# schematic.net
KiCad netlist of a schematic drawn in Altium Designer
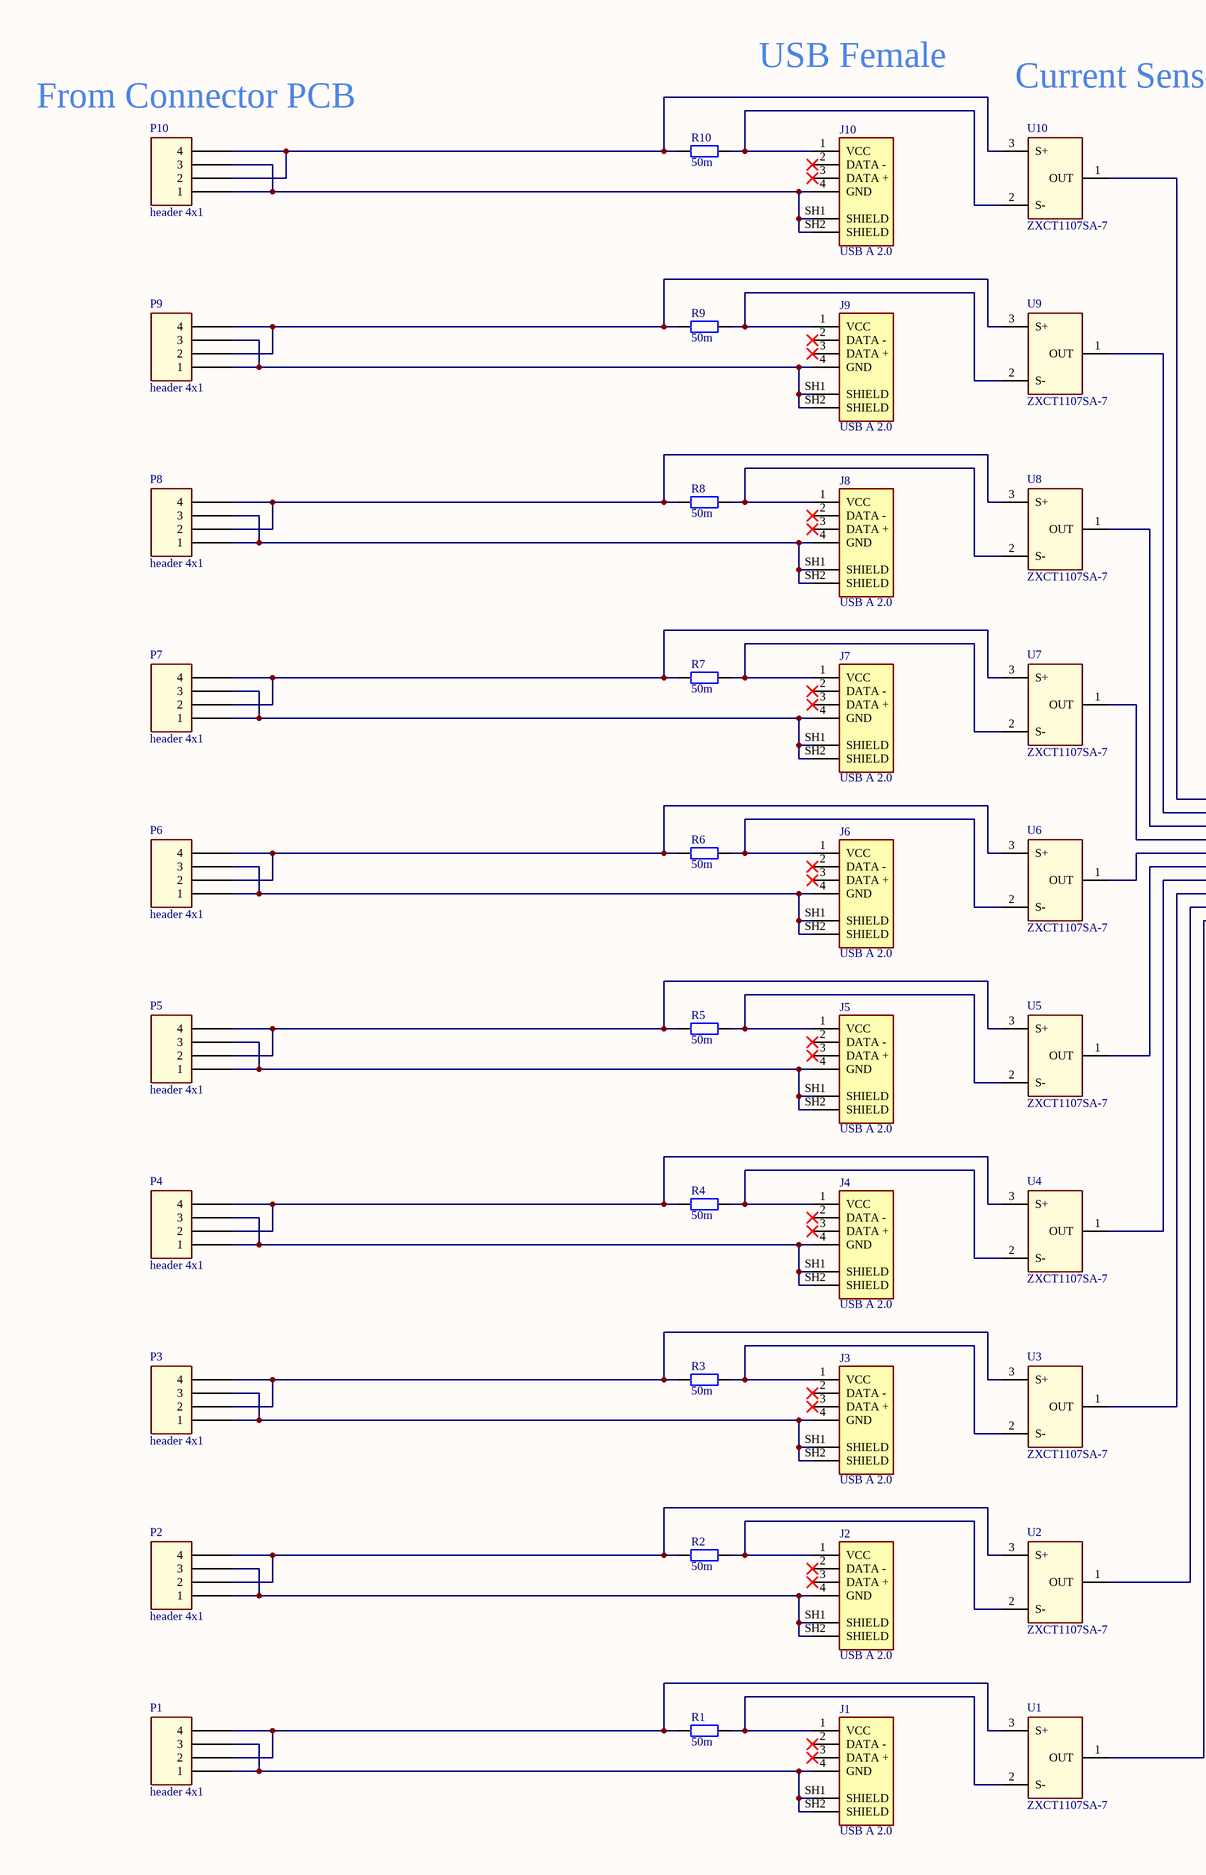
[diagram p0: schematic.SchDoc, left]
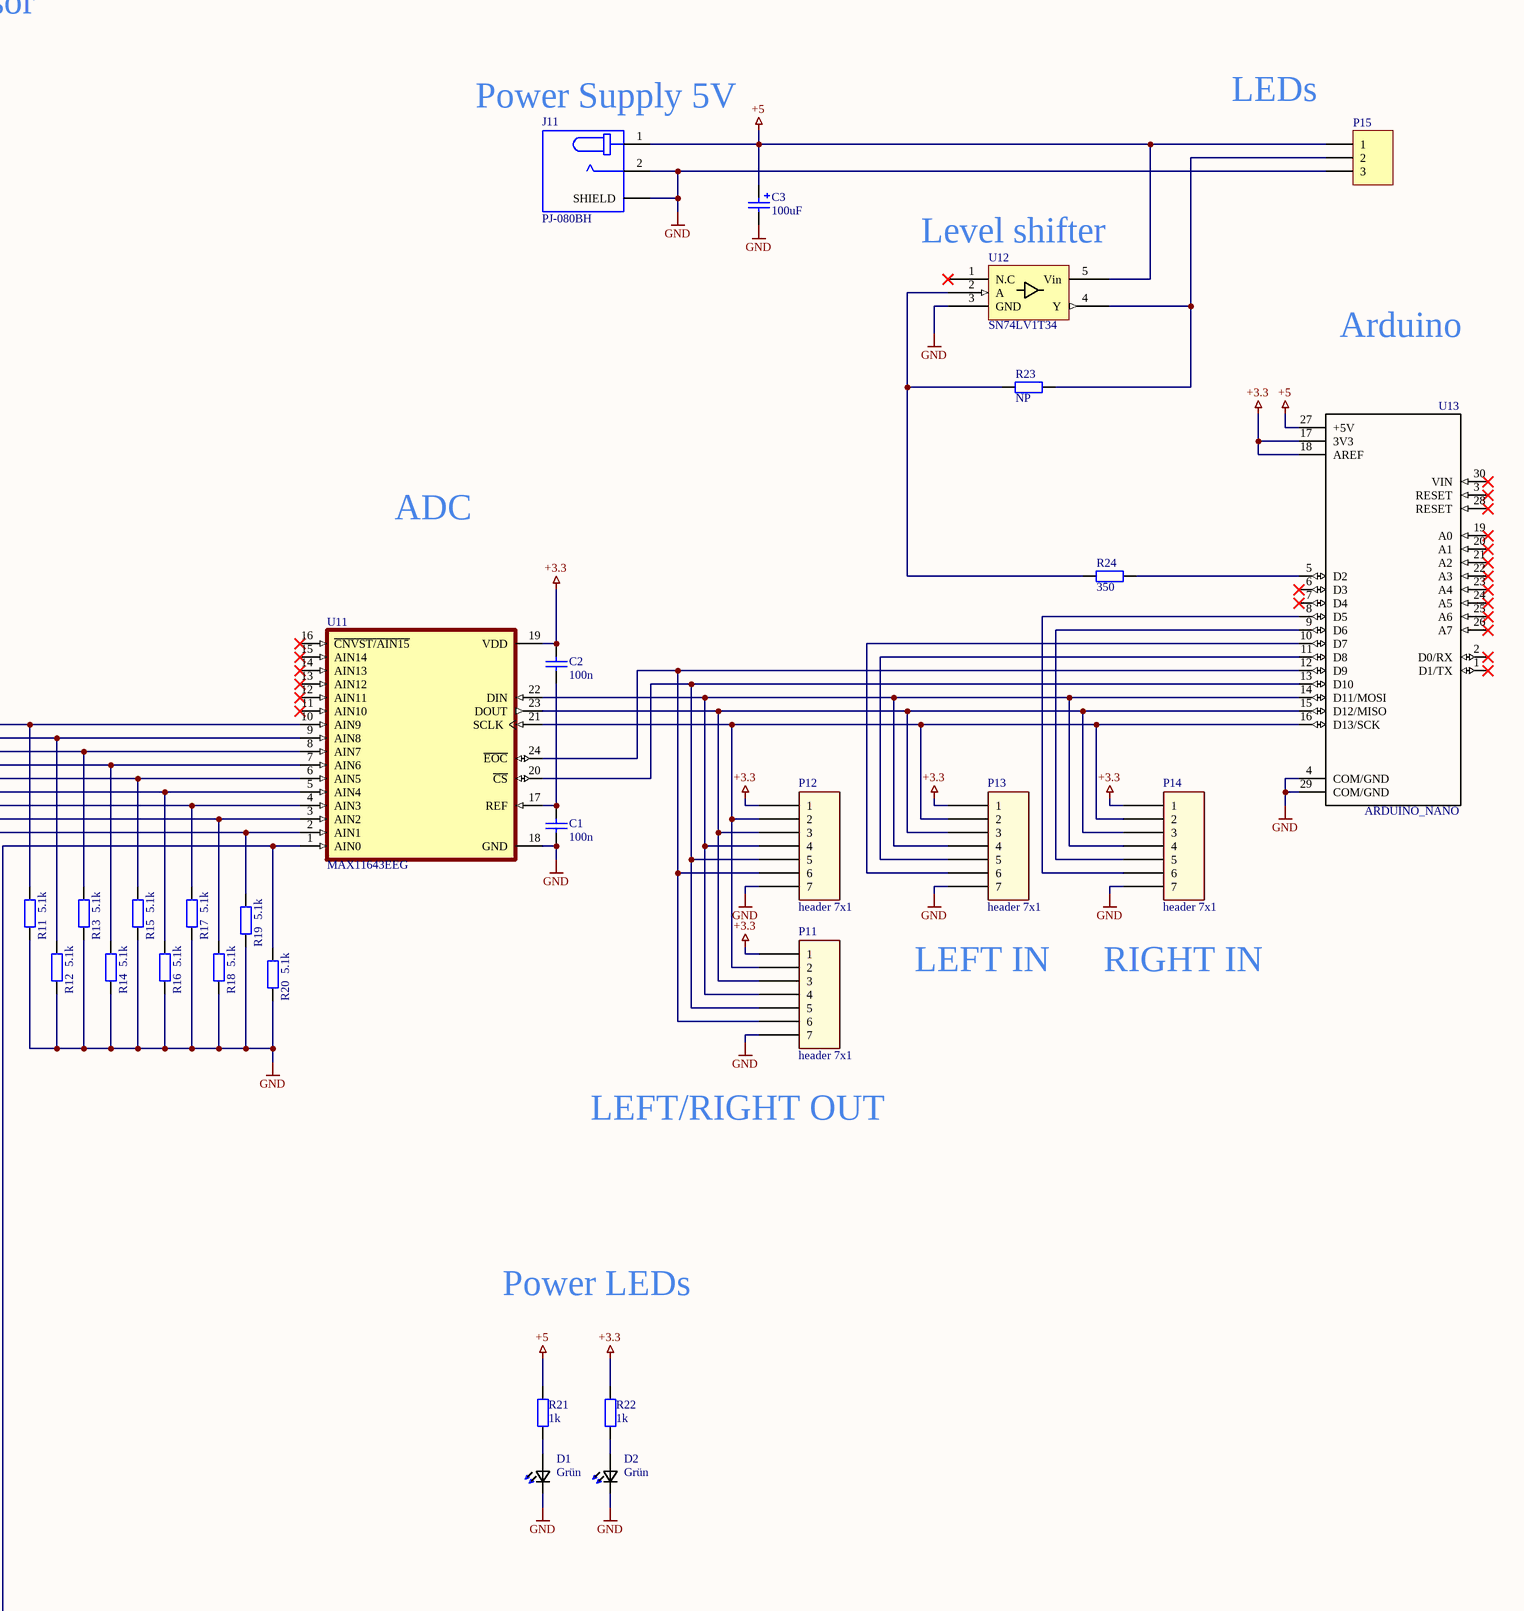
[diagram p1: schematic.SchDoc, right]

(export (version "E")
  (design (tool "Eeschema 10.0.6"))
  (components
    (comp (ref "C1")
      (value "100n")
      (footprint "CAP_0603i_1608m -N")
      (description "capacitor")
      (libsource (lib "IDSC std generic parts") (part "Cap"))
    )
    (comp (ref "C2")
      (value "100n")
      (footprint "CAP_0603i_1608m -N")
      (description "capacitor")
      (libsource (lib "IDSC std generic parts") (part "Cap"))
    )
    (comp (ref "C3")
      (value "100uF")
      (footprint "Cap_F-Type-Package")
      (description "Polarised capacitor (e.g. Electrolytic )")
      (libsource (lib "IDSC std generic parts") (part "Cap pol"))
    )
    (comp (ref "D1")
      (value "Grün")
      (footprint "*0603")
      (description "LED; SMD; 0603; gr黱; 35mcd; 1.6x0.8x0.55mm; 130掳; 2梅2.V; 20mA")
      (fields (field (name "MP") "LTST-C191KGKT") (field (name "DIGI-KEY_PART_NUMBER") "160-1446-1-ND"))
      (libsource (lib "Funk") (part "LTST-C191KGKT"))
    )
    (comp (ref "D2")
      (value "Grün")
      (footprint "*0603")
      (description "LED; SMD; 0603; gr黱; 35mcd; 1.6x0.8x0.55mm; 130掳; 2梅2.V; 20mA")
      (fields (field (name "MP") "LTST-C191KGKT") (field (name "DIGI-KEY_PART_NUMBER") "160-1446-1-ND"))
      (libsource (lib "Funk") (part "LTST-C191KGKT"))
    )
    (comp (ref "J1")
      (value "USB A 2.0")
      (footprint "54-00005")
      (description "Type A, USB 2.0, 1 A, Vertical, Through Hole, USB Receptacle")
      (fields (field (name "MP") "UJ2-AV-2-TH") (field (name "MF") "CUI Devices"))
      (libsource (lib "USBHUB") (part "USB A 2.0"))
    )
    (comp (ref "J2")
      (value "USB A 2.0")
      (footprint "54-00005")
      (description "Type A, USB 2.0, 1 A, Vertical, Through Hole, USB Receptacle")
      (fields (field (name "MP") "UJ2-AV-2-TH") (field (name "MF") "CUI Devices"))
      (libsource (lib "USBHUB") (part "USB A 2.0"))
    )
    (comp (ref "J3")
      (value "USB A 2.0")
      (footprint "54-00005")
      (description "Type A, USB 2.0, 1 A, Vertical, Through Hole, USB Receptacle")
      (fields (field (name "MP") "UJ2-AV-2-TH") (field (name "MF") "CUI Devices"))
      (libsource (lib "USBHUB") (part "USB A 2.0"))
    )
    (comp (ref "J4")
      (value "USB A 2.0")
      (footprint "54-00005")
      (description "Type A, USB 2.0, 1 A, Vertical, Through Hole, USB Receptacle")
      (fields (field (name "MP") "UJ2-AV-2-TH") (field (name "MF") "CUI Devices"))
      (libsource (lib "USBHUB") (part "USB A 2.0"))
    )
    (comp (ref "J5")
      (value "USB A 2.0")
      (footprint "54-00005")
      (description "Type A, USB 2.0, 1 A, Vertical, Through Hole, USB Receptacle")
      (fields (field (name "MP") "UJ2-AV-2-TH") (field (name "MF") "CUI Devices"))
      (libsource (lib "USBHUB") (part "USB A 2.0"))
    )
    (comp (ref "J6")
      (value "USB A 2.0")
      (footprint "54-00005")
      (description "Type A, USB 2.0, 1 A, Vertical, Through Hole, USB Receptacle")
      (fields (field (name "MP") "UJ2-AV-2-TH") (field (name "MF") "CUI Devices"))
      (libsource (lib "USBHUB") (part "USB A 2.0"))
    )
    (comp (ref "J7")
      (value "USB A 2.0")
      (footprint "54-00005")
      (description "Type A, USB 2.0, 1 A, Vertical, Through Hole, USB Receptacle")
      (fields (field (name "MP") "UJ2-AV-2-TH") (field (name "MF") "CUI Devices"))
      (libsource (lib "USBHUB") (part "USB A 2.0"))
    )
    (comp (ref "J8")
      (value "USB A 2.0")
      (footprint "54-00005")
      (description "Type A, USB 2.0, 1 A, Vertical, Through Hole, USB Receptacle")
      (fields (field (name "MP") "UJ2-AV-2-TH") (field (name "MF") "CUI Devices"))
      (libsource (lib "USBHUB") (part "USB A 2.0"))
    )
    (comp (ref "J9")
      (value "USB A 2.0")
      (footprint "54-00005")
      (description "Type A, USB 2.0, 1 A, Vertical, Through Hole, USB Receptacle")
      (fields (field (name "MP") "UJ2-AV-2-TH") (field (name "MF") "CUI Devices"))
      (libsource (lib "USBHUB") (part "USB A 2.0"))
    )
    (comp (ref "J10")
      (value "USB A 2.0")
      (footprint "54-00005")
      (description "Type A, USB 2.0, 1 A, Vertical, Through Hole, USB Receptacle")
      (fields (field (name "MP") "UJ2-AV-2-TH") (field (name "MF") "CUI Devices"))
      (libsource (lib "USBHUB") (part "USB A 2.0"))
    )
    (comp (ref "J11")
      (value "PJ-080BH")
      (footprint "CUI_PJ-080BH")
      (description "2.5 x 6.4 mm, 10.0 A, Horizontal, Through Hole, Shielded, Dc Power Jack Connector")
      (fields (field (name "MF") "CUI Devices"))
      (libsource (lib "USBHUB") (part "PJ-080BH"))
    )
    (comp (ref "P1")
      (value "header 4x1")
      (footprint "4x1, 2.54mm, smd")
      (libsource (lib "USBHUB") (part "header 4x1"))
    )
    (comp (ref "P2")
      (value "header 4x1")
      (footprint "4x1, 2.54mm, smd")
      (libsource (lib "USBHUB") (part "header 4x1"))
    )
    (comp (ref "P3")
      (value "header 4x1")
      (footprint "4x1, 2.54mm, smd")
      (libsource (lib "USBHUB") (part "header 4x1"))
    )
    (comp (ref "P4")
      (value "header 4x1")
      (footprint "4x1, 2.54mm, smd")
      (libsource (lib "USBHUB") (part "header 4x1"))
    )
    (comp (ref "P5")
      (value "header 4x1")
      (footprint "4x1, 2.54mm, smd")
      (libsource (lib "USBHUB") (part "header 4x1"))
    )
    (comp (ref "P6")
      (value "header 4x1")
      (footprint "4x1, 2.54mm, smd")
      (libsource (lib "USBHUB") (part "header 4x1"))
    )
    (comp (ref "P7")
      (value "header 4x1")
      (footprint "4x1, 2.54mm, smd")
      (libsource (lib "USBHUB") (part "header 4x1"))
    )
    (comp (ref "P8")
      (value "header 4x1")
      (footprint "4x1, 2.54mm, smd")
      (libsource (lib "USBHUB") (part "header 4x1"))
    )
    (comp (ref "P9")
      (value "header 4x1")
      (footprint "4x1, 2.54mm, smd")
      (libsource (lib "USBHUB") (part "header 4x1"))
    )
    (comp (ref "P10")
      (value "header 4x1")
      (footprint "4x1, 2.54mm, smd")
      (libsource (lib "USBHUB") (part "header 4x1"))
    )
    (comp (ref "P11")
      (value "header 7x1")
      (footprint "7 pin, 3.5mm")
      (description "right out")
      (libsource (lib "USBHUB") (part "header 7x1"))
    )
    (comp (ref "P12")
      (value "header 7x1")
      (footprint "7 pin, 3.5mm")
      (description "left out")
      (libsource (lib "USBHUB") (part "header 7x1"))
    )
    (comp (ref "P13")
      (value "header 7x1")
      (footprint "7 pin, 3.5mm")
      (description "left in")
      (libsource (lib "USBHUB") (part "header 7x1"))
    )
    (comp (ref "P14")
      (value "header 7x1")
      (footprint "7 pin, 3.5mm")
      (description "right in")
      (libsource (lib "USBHUB") (part "header 7x1"))
    )
    (comp (ref "P15")
      (value "Header 3")
      (footprint "3.5MM Phoenix Contact 1751251")
      (description "Header, 3-Pin")
      (libsource (lib "IDSC std connectors") (part "Header 3"))
    )
    (comp (ref "R1")
      (value "50m")
      (footprint "RES_0805i_2012m -N")
      (description "Resistor")
      (libsource (lib "IDSC std generic parts") (part "Res"))
    )
    (comp (ref "R2")
      (value "50m")
      (footprint "RES_0805i_2012m -N")
      (description "Resistor")
      (libsource (lib "IDSC std generic parts") (part "Res"))
    )
    (comp (ref "R3")
      (value "50m")
      (footprint "RES_0805i_2012m -N")
      (description "Resistor")
      (libsource (lib "IDSC std generic parts") (part "Res"))
    )
    (comp (ref "R4")
      (value "50m")
      (footprint "RES_0805i_2012m -N")
      (description "Resistor")
      (libsource (lib "IDSC std generic parts") (part "Res"))
    )
    (comp (ref "R5")
      (value "50m")
      (footprint "RES_0805i_2012m -N")
      (description "Resistor")
      (libsource (lib "IDSC std generic parts") (part "Res"))
    )
    (comp (ref "R6")
      (value "50m")
      (footprint "RES_0805i_2012m -N")
      (description "Resistor")
      (libsource (lib "IDSC std generic parts") (part "Res"))
    )
    (comp (ref "R7")
      (value "50m")
      (footprint "RES_0805i_2012m -N")
      (description "Resistor")
      (libsource (lib "IDSC std generic parts") (part "Res"))
    )
    (comp (ref "R8")
      (value "50m")
      (footprint "RES_0805i_2012m -N")
      (description "Resistor")
      (libsource (lib "IDSC std generic parts") (part "Res"))
    )
    (comp (ref "R9")
      (value "50m")
      (footprint "RES_0805i_2012m -N")
      (description "Resistor")
      (libsource (lib "IDSC std generic parts") (part "Res"))
    )
    (comp (ref "R10")
      (value "50m")
      (footprint "RES_0805i_2012m -N")
      (description "Resistor")
      (libsource (lib "IDSC std generic parts") (part "Res"))
    )
    (comp (ref "R11")
      (value "5.1k")
      (footprint "RES_0603i_1608m -N")
      (description "Resistor")
      (libsource (lib "") (part "Res_1"))
    )
    (comp (ref "R12")
      (value "5.1k")
      (footprint "RES_0603i_1608m -N")
      (description "Resistor")
      (libsource (lib "") (part "Res_1"))
    )
    (comp (ref "R13")
      (value "5.1k")
      (footprint "RES_0603i_1608m -N")
      (description "Resistor")
      (libsource (lib "") (part "Res_1"))
    )
    (comp (ref "R14")
      (value "5.1k")
      (footprint "RES_0603i_1608m -N")
      (description "Resistor")
      (libsource (lib "") (part "Res_1"))
    )
    (comp (ref "R15")
      (value "5.1k")
      (footprint "RES_0603i_1608m -N")
      (description "Resistor")
      (libsource (lib "") (part "Res_1"))
    )
    (comp (ref "R16")
      (value "5.1k")
      (footprint "RES_0603i_1608m -N")
      (description "Resistor")
      (libsource (lib "") (part "Res_1"))
    )
    (comp (ref "R17")
      (value "5.1k")
      (footprint "RES_0603i_1608m -N")
      (description "Resistor")
      (libsource (lib "") (part "Res_1"))
    )
    (comp (ref "R18")
      (value "5.1k")
      (footprint "RES_0603i_1608m -N")
      (description "Resistor")
      (libsource (lib "") (part "Res_1"))
    )
    (comp (ref "R19")
      (value "5.1k")
      (footprint "RES_0603i_1608m -N")
      (description "Resistor")
      (libsource (lib "") (part "Res_1"))
    )
    (comp (ref "R20")
      (value "5.1k")
      (footprint "RES_0603i_1608m -N")
      (description "Resistor")
      (libsource (lib "") (part "Res_1"))
    )
    (comp (ref "R21")
      (value "1k")
      (footprint "RES_0603i_1608m -N")
      (description "Resistor")
      (libsource (lib "") (part "Res_1"))
    )
    (comp (ref "R22")
      (value "1k")
      (footprint "RES_0603i_1608m -N")
      (description "Resistor")
      (libsource (lib "") (part "Res_1"))
    )
    (comp (ref "R23")
      (value "NP")
      (footprint "RES_0603i_1608m -N")
      (description "Resistor")
      (libsource (lib "IDSC std generic parts") (part "Res"))
    )
    (comp (ref "R24")
      (value "350")
      (footprint "RES_0603i_1608m -N")
      (description "Resistor")
      (libsource (lib "IDSC std generic parts") (part "Res"))
    )
    (comp (ref "U1")
      (value "ZXCT1107SA-7")
      (footprint "SOT-23-M")
      (libsource (lib "USBHUB") (part "ZXCT1107SA-7"))
    )
    (comp (ref "U2")
      (value "ZXCT1107SA-7")
      (footprint "SOT-23-M")
      (libsource (lib "USBHUB") (part "ZXCT1107SA-7"))
    )
    (comp (ref "U3")
      (value "ZXCT1107SA-7")
      (footprint "SOT-23-M")
      (libsource (lib "USBHUB") (part "ZXCT1107SA-7"))
    )
    (comp (ref "U4")
      (value "ZXCT1107SA-7")
      (footprint "SOT-23-M")
      (libsource (lib "USBHUB") (part "ZXCT1107SA-7"))
    )
    (comp (ref "U5")
      (value "ZXCT1107SA-7")
      (footprint "SOT-23-M")
      (libsource (lib "USBHUB") (part "ZXCT1107SA-7"))
    )
    (comp (ref "U6")
      (value "ZXCT1107SA-7")
      (footprint "SOT-23-M")
      (libsource (lib "USBHUB") (part "ZXCT1107SA-7"))
    )
    (comp (ref "U7")
      (value "ZXCT1107SA-7")
      (footprint "SOT-23-M")
      (libsource (lib "USBHUB") (part "ZXCT1107SA-7"))
    )
    (comp (ref "U8")
      (value "ZXCT1107SA-7")
      (footprint "SOT-23-M")
      (libsource (lib "USBHUB") (part "ZXCT1107SA-7"))
    )
    (comp (ref "U9")
      (value "ZXCT1107SA-7")
      (footprint "SOT-23-M")
      (libsource (lib "USBHUB") (part "ZXCT1107SA-7"))
    )
    (comp (ref "U10")
      (value "ZXCT1107SA-7")
      (footprint "SOT-23-M")
      (libsource (lib "USBHUB") (part "ZXCT1107SA-7"))
    )
    (comp (ref "U11")
      (value "MAX11643EEG")
      (footprint "SOP63P602X175-24N")
      (description "8 Bit Analog to Digital Converter 16 Input 1 SAR 24-QSOP")
      (fields (field (name "MP") "MAX11642EEG+") (field (name "MF") "Maxim Integrated"))
      (libsource (lib "USBHUB") (part "MAX11642EEG"))
    )
    (comp (ref "U12")
      (value "SN74LV1T34")
      (footprint "SOT23-5-N")
      (description "Single Power Supply Single Buffer GATE CMOS Logic Level Shifter")
      (fields (field (name "MANUFACTUER PART NUMBER") "SN74LV1T34DCKR") (field (name "MANUFACTURER") "TI"))
      (libsource (lib "IDSC_component_lib") (part "SN74LV1T34"))
    )
    (comp (ref "U13")
      (value "ARDUINO_NANO")
      (footprint "*SHIELD_ARDUINO_NANO")
      (description "Dev.kit: Arduino; UART; ICSP, USB B mini, pin strips")
      (fields (field (name "MF") "Arduino") (field (name "MP") "ARDUINO NANO"))
      (libsource (lib "USBHUB") (part "ARDUINO_NANO"))
    )
  )
  (nets
    (net (code "1") (name "+3.3") (class "Default")
      (node (ref "C2") (pin "2") (pinfunction "2_2") (pintype "passive"))
      (node (ref "P11") (pin "1") (pinfunction "1_1") (pintype "passive"))
      (node (ref "P12") (pin "1") (pinfunction "1_1") (pintype "passive"))
      (node (ref "P13") (pin "1") (pinfunction "1_1") (pintype "passive"))
      (node (ref "P14") (pin "1") (pinfunction "1_1") (pintype "passive"))
      (node (ref "R22") (pin "2") (pinfunction "2_2") (pintype "passive"))
      (node (ref "U11") (pin "19") (pinfunction "VDD_19") (pintype "power_in"))
      (node (ref "U13") (pin "17") (pinfunction "3V3_17") (pintype "power_in"))
      (node (ref "U13") (pin "18") (pinfunction "AREF_18") (pintype "power_in"))
    )
    (net (code "2") (name "+5") (class "Default")
      (node (ref "C3") (pin "1") (pinfunction "1_1") (pintype "passive"))
      (node (ref "J11") (pin "1") (pinfunction "1_1") (pintype "passive"))
      (node (ref "P15") (pin "1") (pinfunction "1_1") (pintype "passive"))
      (node (ref "R21") (pin "2") (pinfunction "2_2") (pintype "passive"))
      (node (ref "U12") (pin "5") (pinfunction "Vin_5") (pintype "power_in"))
      (node (ref "U13") (pin "27") (pinfunction "+5V_27") (pintype "power_in"))
    )
    (net (code "3") (name "GND") (class "Default")
      (node (ref "C1") (pin "1") (pinfunction "1_1") (pintype "passive"))
      (node (ref "C3") (pin "2") (pinfunction "2_2") (pintype "passive"))
      (node (ref "D1") (pin "1") (pinfunction "K2_1") (pintype "passive"))
      (node (ref "D2") (pin "1") (pinfunction "K2_1") (pintype "passive"))
      (node (ref "J11") (pin "2") (pinfunction "2_2") (pintype "passive"))
      (node (ref "J11") (pin "3") (pinfunction "SHIELD_3") (pintype "passive"))
      (node (ref "P11") (pin "7") (pinfunction "7_7") (pintype "passive"))
      (node (ref "P12") (pin "7") (pinfunction "7_7") (pintype "passive"))
      (node (ref "P13") (pin "7") (pinfunction "7_7") (pintype "passive"))
      (node (ref "P14") (pin "7") (pinfunction "7_7") (pintype "passive"))
      (node (ref "P15") (pin "3") (pinfunction "3_3") (pintype "passive"))
      (node (ref "R11") (pin "1") (pinfunction "1_1") (pintype "passive"))
      (node (ref "R12") (pin "1") (pinfunction "1_1") (pintype "passive"))
      (node (ref "R13") (pin "1") (pinfunction "1_1") (pintype "passive"))
      (node (ref "R14") (pin "1") (pinfunction "1_1") (pintype "passive"))
      (node (ref "R15") (pin "1") (pinfunction "1_1") (pintype "passive"))
      (node (ref "R16") (pin "1") (pinfunction "1_1") (pintype "passive"))
      (node (ref "R17") (pin "1") (pinfunction "1_1") (pintype "passive"))
      (node (ref "R18") (pin "1") (pinfunction "1_1") (pintype "passive"))
      (node (ref "R19") (pin "1") (pinfunction "1_1") (pintype "passive"))
      (node (ref "R20") (pin "1") (pinfunction "1_1") (pintype "passive"))
      (node (ref "U11") (pin "18") (pinfunction "GND_18") (pintype "power_in"))
      (node (ref "U12") (pin "3") (pinfunction "GND_3") (pintype "power_in"))
      (node (ref "U13") (pin "29") (pinfunction "COM/GND_29") (pintype "power_in"))
      (node (ref "U13") (pin "4") (pinfunction "COM/GND_4") (pintype "power_in"))
    )
    (net (code "4") (name "Net-(D1-A2)") (class "Default")
      (node (ref "D1") (pin "2") (pinfunction "A2_2") (pintype "passive"))
      (node (ref "R21") (pin "1") (pinfunction "1_1") (pintype "passive"))
    )
    (net (code "5") (name "Net-(D2-A2)") (class "Default")
      (node (ref "D2") (pin "2") (pinfunction "A2_2") (pintype "passive"))
      (node (ref "R22") (pin "1") (pinfunction "1_1") (pintype "passive"))
    )
    (net (code "6") (name "Net-(J1-GND)") (class "Default")
      (node (ref "J1") (pin "4") (pinfunction "GND_4") (pintype "passive"))
      (node (ref "J1") (pin "SH1") (pinfunction "SHIELD_SH1") (pintype "passive"))
      (node (ref "J1") (pin "SH2") (pinfunction "SHIELD_SH2") (pintype "passive"))
      (node (ref "P1") (pin "1") (pinfunction "1_1") (pintype "passive"))
      (node (ref "P1") (pin "3") (pinfunction "3_3") (pintype "passive"))
    )
    (net (code "7") (name "Net-(J1-VCC)") (class "Default")
      (node (ref "J1") (pin "1") (pinfunction "VCC_1") (pintype "passive"))
      (node (ref "R1") (pin "2") (pinfunction "2_2") (pintype "passive"))
      (node (ref "U1") (pin "2") (pinfunction "S-_2") (pintype "passive"))
    )
    (net (code "8") (name "Net-(J2-GND)") (class "Default")
      (node (ref "J2") (pin "4") (pinfunction "GND_4") (pintype "passive"))
      (node (ref "J2") (pin "SH1") (pinfunction "SHIELD_SH1") (pintype "passive"))
      (node (ref "J2") (pin "SH2") (pinfunction "SHIELD_SH2") (pintype "passive"))
      (node (ref "P2") (pin "1") (pinfunction "1_1") (pintype "passive"))
      (node (ref "P2") (pin "3") (pinfunction "3_3") (pintype "passive"))
    )
    (net (code "9") (name "Net-(J2-VCC)") (class "Default")
      (node (ref "J2") (pin "1") (pinfunction "VCC_1") (pintype "passive"))
      (node (ref "R2") (pin "2") (pinfunction "2_2") (pintype "passive"))
      (node (ref "U2") (pin "2") (pinfunction "S-_2") (pintype "passive"))
    )
    (net (code "10") (name "Net-(J3-GND)") (class "Default")
      (node (ref "J3") (pin "4") (pinfunction "GND_4") (pintype "passive"))
      (node (ref "J3") (pin "SH1") (pinfunction "SHIELD_SH1") (pintype "passive"))
      (node (ref "J3") (pin "SH2") (pinfunction "SHIELD_SH2") (pintype "passive"))
      (node (ref "P3") (pin "1") (pinfunction "1_1") (pintype "passive"))
      (node (ref "P3") (pin "3") (pinfunction "3_3") (pintype "passive"))
    )
    (net (code "11") (name "Net-(J3-VCC)") (class "Default")
      (node (ref "J3") (pin "1") (pinfunction "VCC_1") (pintype "passive"))
      (node (ref "R3") (pin "2") (pinfunction "2_2") (pintype "passive"))
      (node (ref "U3") (pin "2") (pinfunction "S-_2") (pintype "passive"))
    )
    (net (code "12") (name "Net-(J4-GND)") (class "Default")
      (node (ref "J4") (pin "4") (pinfunction "GND_4") (pintype "passive"))
      (node (ref "J4") (pin "SH1") (pinfunction "SHIELD_SH1") (pintype "passive"))
      (node (ref "J4") (pin "SH2") (pinfunction "SHIELD_SH2") (pintype "passive"))
      (node (ref "P4") (pin "1") (pinfunction "1_1") (pintype "passive"))
      (node (ref "P4") (pin "3") (pinfunction "3_3") (pintype "passive"))
    )
    (net (code "13") (name "Net-(J4-VCC)") (class "Default")
      (node (ref "J4") (pin "1") (pinfunction "VCC_1") (pintype "passive"))
      (node (ref "R4") (pin "2") (pinfunction "2_2") (pintype "passive"))
      (node (ref "U4") (pin "2") (pinfunction "S-_2") (pintype "passive"))
    )
    (net (code "14") (name "Net-(J5-GND)") (class "Default")
      (node (ref "J5") (pin "4") (pinfunction "GND_4") (pintype "passive"))
      (node (ref "J5") (pin "SH1") (pinfunction "SHIELD_SH1") (pintype "passive"))
      (node (ref "J5") (pin "SH2") (pinfunction "SHIELD_SH2") (pintype "passive"))
      (node (ref "P5") (pin "1") (pinfunction "1_1") (pintype "passive"))
      (node (ref "P5") (pin "3") (pinfunction "3_3") (pintype "passive"))
    )
    (net (code "15") (name "Net-(J5-VCC)") (class "Default")
      (node (ref "J5") (pin "1") (pinfunction "VCC_1") (pintype "passive"))
      (node (ref "R5") (pin "2") (pinfunction "2_2") (pintype "passive"))
      (node (ref "U5") (pin "2") (pinfunction "S-_2") (pintype "passive"))
    )
    (net (code "16") (name "Net-(J6-GND)") (class "Default")
      (node (ref "J6") (pin "4") (pinfunction "GND_4") (pintype "passive"))
      (node (ref "J6") (pin "SH1") (pinfunction "SHIELD_SH1") (pintype "passive"))
      (node (ref "J6") (pin "SH2") (pinfunction "SHIELD_SH2") (pintype "passive"))
      (node (ref "P6") (pin "1") (pinfunction "1_1") (pintype "passive"))
      (node (ref "P6") (pin "3") (pinfunction "3_3") (pintype "passive"))
    )
    (net (code "17") (name "Net-(J6-VCC)") (class "Default")
      (node (ref "J6") (pin "1") (pinfunction "VCC_1") (pintype "passive"))
      (node (ref "R6") (pin "2") (pinfunction "2_2") (pintype "passive"))
      (node (ref "U6") (pin "2") (pinfunction "S-_2") (pintype "passive"))
    )
    (net (code "18") (name "Net-(J7-GND)") (class "Default")
      (node (ref "J7") (pin "4") (pinfunction "GND_4") (pintype "passive"))
      (node (ref "J7") (pin "SH1") (pinfunction "SHIELD_SH1") (pintype "passive"))
      (node (ref "J7") (pin "SH2") (pinfunction "SHIELD_SH2") (pintype "passive"))
      (node (ref "P7") (pin "1") (pinfunction "1_1") (pintype "passive"))
      (node (ref "P7") (pin "3") (pinfunction "3_3") (pintype "passive"))
    )
    (net (code "19") (name "Net-(J7-VCC)") (class "Default")
      (node (ref "J7") (pin "1") (pinfunction "VCC_1") (pintype "passive"))
      (node (ref "R7") (pin "2") (pinfunction "2_2") (pintype "passive"))
      (node (ref "U7") (pin "2") (pinfunction "S-_2") (pintype "passive"))
    )
    (net (code "20") (name "Net-(J8-GND)") (class "Default")
      (node (ref "J8") (pin "4") (pinfunction "GND_4") (pintype "passive"))
      (node (ref "J8") (pin "SH1") (pinfunction "SHIELD_SH1") (pintype "passive"))
      (node (ref "J8") (pin "SH2") (pinfunction "SHIELD_SH2") (pintype "passive"))
      (node (ref "P8") (pin "1") (pinfunction "1_1") (pintype "passive"))
      (node (ref "P8") (pin "3") (pinfunction "3_3") (pintype "passive"))
    )
    (net (code "21") (name "Net-(J8-VCC)") (class "Default")
      (node (ref "J8") (pin "1") (pinfunction "VCC_1") (pintype "passive"))
      (node (ref "R8") (pin "2") (pinfunction "2_2") (pintype "passive"))
      (node (ref "U8") (pin "2") (pinfunction "S-_2") (pintype "passive"))
    )
    (net (code "22") (name "Net-(J9-GND)") (class "Default")
      (node (ref "J9") (pin "4") (pinfunction "GND_4") (pintype "passive"))
      (node (ref "J9") (pin "SH1") (pinfunction "SHIELD_SH1") (pintype "passive"))
      (node (ref "J9") (pin "SH2") (pinfunction "SHIELD_SH2") (pintype "passive"))
      (node (ref "P9") (pin "1") (pinfunction "1_1") (pintype "passive"))
      (node (ref "P9") (pin "3") (pinfunction "3_3") (pintype "passive"))
    )
    (net (code "23") (name "Net-(J9-VCC)") (class "Default")
      (node (ref "J9") (pin "1") (pinfunction "VCC_1") (pintype "passive"))
      (node (ref "R9") (pin "2") (pinfunction "2_2") (pintype "passive"))
      (node (ref "U9") (pin "2") (pinfunction "S-_2") (pintype "passive"))
    )
    (net (code "24") (name "Net-(J10-GND)") (class "Default")
      (node (ref "J10") (pin "4") (pinfunction "GND_4") (pintype "passive"))
      (node (ref "J10") (pin "SH1") (pinfunction "SHIELD_SH1") (pintype "passive"))
      (node (ref "J10") (pin "SH2") (pinfunction "SHIELD_SH2") (pintype "passive"))
      (node (ref "P10") (pin "1") (pinfunction "1_1") (pintype "passive"))
      (node (ref "P10") (pin "3") (pinfunction "3_3") (pintype "passive"))
    )
    (net (code "25") (name "Net-(J10-VCC)") (class "Default")
      (node (ref "J10") (pin "1") (pinfunction "VCC_1") (pintype "passive"))
      (node (ref "R10") (pin "2") (pinfunction "2_2") (pintype "passive"))
      (node (ref "U10") (pin "2") (pinfunction "S-_2") (pintype "passive"))
    )
    (net (code "26") (name "Net-(U1-OUT)") (class "Default")
      (node (ref "R20") (pin "2") (pinfunction "2_2") (pintype "passive"))
      (node (ref "U1") (pin "1") (pinfunction "OUT_1") (pintype "passive"))
      (node (ref "U11") (pin "1") (pinfunction "AIN0_1") (pintype "input"))
    )
    (net (code "27") (name "Net-(U1-S+)") (class "Default")
      (node (ref "P1") (pin "2") (pinfunction "2_2") (pintype "passive"))
      (node (ref "P1") (pin "4") (pinfunction "4_4") (pintype "passive"))
      (node (ref "R1") (pin "1") (pinfunction "1_1") (pintype "passive"))
      (node (ref "U1") (pin "3") (pinfunction "S+_3") (pintype "passive"))
    )
    (net (code "28") (name "Net-(U2-S+)") (class "Default")
      (node (ref "P2") (pin "2") (pinfunction "2_2") (pintype "passive"))
      (node (ref "P2") (pin "4") (pinfunction "4_4") (pintype "passive"))
      (node (ref "R2") (pin "1") (pinfunction "1_1") (pintype "passive"))
      (node (ref "U2") (pin "3") (pinfunction "S+_3") (pintype "passive"))
    )
    (net (code "29") (name "Net-(U3-S+)") (class "Default")
      (node (ref "P3") (pin "2") (pinfunction "2_2") (pintype "passive"))
      (node (ref "P3") (pin "4") (pinfunction "4_4") (pintype "passive"))
      (node (ref "R3") (pin "1") (pinfunction "1_1") (pintype "passive"))
      (node (ref "U3") (pin "3") (pinfunction "S+_3") (pintype "passive"))
    )
    (net (code "30") (name "Net-(U4-S+)") (class "Default")
      (node (ref "P4") (pin "2") (pinfunction "2_2") (pintype "passive"))
      (node (ref "P4") (pin "4") (pinfunction "4_4") (pintype "passive"))
      (node (ref "R4") (pin "1") (pinfunction "1_1") (pintype "passive"))
      (node (ref "U4") (pin "3") (pinfunction "S+_3") (pintype "passive"))
    )
    (net (code "31") (name "Net-(U5-S+)") (class "Default")
      (node (ref "P5") (pin "2") (pinfunction "2_2") (pintype "passive"))
      (node (ref "P5") (pin "4") (pinfunction "4_4") (pintype "passive"))
      (node (ref "R5") (pin "1") (pinfunction "1_1") (pintype "passive"))
      (node (ref "U5") (pin "3") (pinfunction "S+_3") (pintype "passive"))
    )
    (net (code "32") (name "Net-(U6-S+)") (class "Default")
      (node (ref "P6") (pin "2") (pinfunction "2_2") (pintype "passive"))
      (node (ref "P6") (pin "4") (pinfunction "4_4") (pintype "passive"))
      (node (ref "R6") (pin "1") (pinfunction "1_1") (pintype "passive"))
      (node (ref "U6") (pin "3") (pinfunction "S+_3") (pintype "passive"))
    )
    (net (code "33") (name "Net-(U7-S+)") (class "Default")
      (node (ref "P7") (pin "2") (pinfunction "2_2") (pintype "passive"))
      (node (ref "P7") (pin "4") (pinfunction "4_4") (pintype "passive"))
      (node (ref "R7") (pin "1") (pinfunction "1_1") (pintype "passive"))
      (node (ref "U7") (pin "3") (pinfunction "S+_3") (pintype "passive"))
    )
    (net (code "34") (name "Net-(U8-S+)") (class "Default")
      (node (ref "P8") (pin "2") (pinfunction "2_2") (pintype "passive"))
      (node (ref "P8") (pin "4") (pinfunction "4_4") (pintype "passive"))
      (node (ref "R8") (pin "1") (pinfunction "1_1") (pintype "passive"))
      (node (ref "U8") (pin "3") (pinfunction "S+_3") (pintype "passive"))
    )
    (net (code "35") (name "Net-(U9-S+)") (class "Default")
      (node (ref "P9") (pin "2") (pinfunction "2_2") (pintype "passive"))
      (node (ref "P9") (pin "4") (pinfunction "4_4") (pintype "passive"))
      (node (ref "R9") (pin "1") (pinfunction "1_1") (pintype "passive"))
      (node (ref "U9") (pin "3") (pinfunction "S+_3") (pintype "passive"))
    )
    (net (code "36") (name "Net-(U10-OUT)") (class "Default")
      (node (ref "R11") (pin "2") (pinfunction "2_2") (pintype "passive"))
      (node (ref "U10") (pin "1") (pinfunction "OUT_1") (pintype "passive"))
      (node (ref "U11") (pin "10") (pinfunction "AIN9_10") (pintype "input"))
    )
    (net (code "37") (name "Net-(U10-S+)") (class "Default")
      (node (ref "P10") (pin "2") (pinfunction "2_2") (pintype "passive"))
      (node (ref "P10") (pin "4") (pinfunction "4_4") (pintype "passive"))
      (node (ref "R10") (pin "1") (pinfunction "1_1") (pintype "passive"))
      (node (ref "U10") (pin "3") (pinfunction "S+_3") (pintype "passive"))
    )
    (net (code "38") (name "Net-(U11-AIN1)") (class "Default")
      (node (ref "R19") (pin "2") (pinfunction "2_2") (pintype "passive"))
      (node (ref "U11") (pin "2") (pinfunction "AIN1_2") (pintype "input"))
      (node (ref "U2") (pin "1") (pinfunction "OUT_1") (pintype "passive"))
    )
    (net (code "39") (name "Net-(U11-AIN2)") (class "Default")
      (node (ref "R18") (pin "2") (pinfunction "2_2") (pintype "passive"))
      (node (ref "U11") (pin "3") (pinfunction "AIN2_3") (pintype "input"))
      (node (ref "U3") (pin "1") (pinfunction "OUT_1") (pintype "passive"))
    )
    (net (code "40") (name "Net-(U11-AIN3)") (class "Default")
      (node (ref "R17") (pin "2") (pinfunction "2_2") (pintype "passive"))
      (node (ref "U11") (pin "4") (pinfunction "AIN3_4") (pintype "input"))
      (node (ref "U4") (pin "1") (pinfunction "OUT_1") (pintype "passive"))
    )
    (net (code "41") (name "Net-(U11-AIN4)") (class "Default")
      (node (ref "R16") (pin "2") (pinfunction "2_2") (pintype "passive"))
      (node (ref "U11") (pin "5") (pinfunction "AIN4_5") (pintype "input"))
      (node (ref "U5") (pin "1") (pinfunction "OUT_1") (pintype "passive"))
    )
    (net (code "42") (name "Net-(U11-AIN5)") (class "Default")
      (node (ref "R15") (pin "2") (pinfunction "2_2") (pintype "passive"))
      (node (ref "U11") (pin "6") (pinfunction "AIN5_6") (pintype "input"))
      (node (ref "U6") (pin "1") (pinfunction "OUT_1") (pintype "passive"))
    )
    (net (code "43") (name "Net-(U11-AIN6)") (class "Default")
      (node (ref "R14") (pin "2") (pinfunction "2_2") (pintype "passive"))
      (node (ref "U11") (pin "7") (pinfunction "AIN6_7") (pintype "input"))
      (node (ref "U7") (pin "1") (pinfunction "OUT_1") (pintype "passive"))
    )
    (net (code "44") (name "Net-(U11-AIN7)") (class "Default")
      (node (ref "R13") (pin "2") (pinfunction "2_2") (pintype "passive"))
      (node (ref "U11") (pin "8") (pinfunction "AIN7_8") (pintype "input"))
      (node (ref "U8") (pin "1") (pinfunction "OUT_1") (pintype "passive"))
    )
    (net (code "45") (name "Net-(U11-AIN8)") (class "Default")
      (node (ref "R12") (pin "2") (pinfunction "2_2") (pintype "passive"))
      (node (ref "U11") (pin "9") (pinfunction "AIN8_9") (pintype "input"))
      (node (ref "U9") (pin "1") (pinfunction "OUT_1") (pintype "passive"))
    )
    (net (code "46") (name "Net-(U11-DIN)") (class "Default")
      (node (ref "P11") (pin "4") (pinfunction "4_4") (pintype "passive"))
      (node (ref "P12") (pin "4") (pinfunction "4_4") (pintype "passive"))
      (node (ref "P13") (pin "4") (pinfunction "4_4") (pintype "passive"))
      (node (ref "P14") (pin "4") (pinfunction "4_4") (pintype "passive"))
      (node (ref "U11") (pin "22") (pinfunction "DIN_22") (pintype "input"))
      (node (ref "U13") (pin "14") (pinfunction "D11/MOSI_14") (pintype "bidirectional"))
    )
    (net (code "47") (name "Net-(U11-DOUT)") (class "Default")
      (node (ref "P11") (pin "3") (pinfunction "3_3") (pintype "passive"))
      (node (ref "P12") (pin "3") (pinfunction "3_3") (pintype "passive"))
      (node (ref "P13") (pin "3") (pinfunction "3_3") (pintype "passive"))
      (node (ref "P14") (pin "3") (pinfunction "3_3") (pintype "passive"))
      (node (ref "U11") (pin "23") (pinfunction "DOUT_23") (pintype "output"))
      (node (ref "U13") (pin "15") (pinfunction "D12/MISO_15") (pintype "bidirectional"))
    )
    (net (code "48") (name "Net-(U11-REF)") (class "Default")
      (node (ref "C1") (pin "2") (pinfunction "2_2") (pintype "passive"))
      (node (ref "C2") (pin "1") (pinfunction "1_1") (pintype "passive"))
      (node (ref "U11") (pin "17") (pinfunction "REF_17") (pintype "input"))
    )
    (net (code "49") (name "Net-(U11-SCLK)") (class "Default")
      (node (ref "P11") (pin "2") (pinfunction "2_2") (pintype "passive"))
      (node (ref "P12") (pin "2") (pinfunction "2_2") (pintype "passive"))
      (node (ref "P13") (pin "2") (pinfunction "2_2") (pintype "passive"))
      (node (ref "P14") (pin "2") (pinfunction "2_2") (pintype "passive"))
      (node (ref "U11") (pin "21") (pinfunction "SCLK_21") (pintype "input"))
      (node (ref "U13") (pin "16") (pinfunction "D13/SCK_16") (pintype "bidirectional"))
    )
    (net (code "50") (name "Net-(U11-~{CS})") (class "Default")
      (node (ref "P11") (pin "5") (pinfunction "5_5") (pintype "passive"))
      (node (ref "P12") (pin "5") (pinfunction "5_5") (pintype "passive"))
      (node (ref "U11") (pin "20") (pinfunction "~{CS}_20") (pintype "bidirectional"))
      (node (ref "U13") (pin "13") (pinfunction "D10_13") (pintype "bidirectional"))
    )
    (net (code "51") (name "Net-(U11-~{EOC})") (class "Default")
      (node (ref "P11") (pin "6") (pinfunction "6_6") (pintype "passive"))
      (node (ref "P12") (pin "6") (pinfunction "6_6") (pintype "passive"))
      (node (ref "U11") (pin "24") (pinfunction "~{EOC}_24") (pintype "bidirectional"))
      (node (ref "U13") (pin "12") (pinfunction "D9_12") (pintype "bidirectional"))
    )
    (net (code "52") (name "Net-(U12-A)") (class "Default")
      (node (ref "R23") (pin "1") (pinfunction "1_1") (pintype "passive"))
      (node (ref "R24") (pin "1") (pinfunction "1_1") (pintype "passive"))
      (node (ref "U12") (pin "2") (pinfunction "A_2") (pintype "input"))
    )
    (net (code "53") (name "Net-(U12-Y)") (class "Default")
      (node (ref "P15") (pin "2") (pinfunction "2_2") (pintype "passive"))
      (node (ref "R23") (pin "2") (pinfunction "2_2") (pintype "passive"))
      (node (ref "U12") (pin "4") (pinfunction "Y_4") (pintype "output"))
    )
    (net (code "54") (name "Net-(U13-D2)") (class "Default")
      (node (ref "R24") (pin "2") (pinfunction "2_2") (pintype "passive"))
      (node (ref "U13") (pin "5") (pinfunction "D2_5") (pintype "bidirectional"))
    )
    (net (code "55") (name "Net-(U13-D5)") (class "Default")
      (node (ref "P14") (pin "6") (pinfunction "6_6") (pintype "passive"))
      (node (ref "U13") (pin "8") (pinfunction "D5_8") (pintype "bidirectional"))
    )
    (net (code "56") (name "Net-(U13-D6)") (class "Default")
      (node (ref "P14") (pin "5") (pinfunction "5_5") (pintype "passive"))
      (node (ref "U13") (pin "9") (pinfunction "D6_9") (pintype "bidirectional"))
    )
    (net (code "57") (name "Net-(U13-D7)") (class "Default")
      (node (ref "P13") (pin "6") (pinfunction "6_6") (pintype "passive"))
      (node (ref "U13") (pin "10") (pinfunction "D7_10") (pintype "bidirectional"))
    )
    (net (code "58") (name "Net-(U13-D8)") (class "Default")
      (node (ref "P13") (pin "5") (pinfunction "5_5") (pintype "passive"))
      (node (ref "U13") (pin "11") (pinfunction "D8_11") (pintype "bidirectional"))
    )
    (net (code "59") (name "unconnected-(J1-DATA_+-Pad3)") (class "Default")
      (node (ref "J1") (pin "3") (pinfunction "DATA_+_3") (pintype "passive+no_connect"))
    )
    (net (code "60") (name "unconnected-(J1-DATA_--Pad2)") (class "Default")
      (node (ref "J1") (pin "2") (pinfunction "DATA_-_2") (pintype "passive+no_connect"))
    )
    (net (code "61") (name "unconnected-(J2-DATA_+-Pad3)") (class "Default")
      (node (ref "J2") (pin "3") (pinfunction "DATA_+_3") (pintype "passive+no_connect"))
    )
    (net (code "62") (name "unconnected-(J2-DATA_--Pad2)") (class "Default")
      (node (ref "J2") (pin "2") (pinfunction "DATA_-_2") (pintype "passive+no_connect"))
    )
    (net (code "63") (name "unconnected-(J3-DATA_+-Pad3)") (class "Default")
      (node (ref "J3") (pin "3") (pinfunction "DATA_+_3") (pintype "passive+no_connect"))
    )
    (net (code "64") (name "unconnected-(J3-DATA_--Pad2)") (class "Default")
      (node (ref "J3") (pin "2") (pinfunction "DATA_-_2") (pintype "passive+no_connect"))
    )
    (net (code "65") (name "unconnected-(J4-DATA_+-Pad3)") (class "Default")
      (node (ref "J4") (pin "3") (pinfunction "DATA_+_3") (pintype "passive+no_connect"))
    )
    (net (code "66") (name "unconnected-(J4-DATA_--Pad2)") (class "Default")
      (node (ref "J4") (pin "2") (pinfunction "DATA_-_2") (pintype "passive+no_connect"))
    )
    (net (code "67") (name "unconnected-(J5-DATA_+-Pad3)") (class "Default")
      (node (ref "J5") (pin "3") (pinfunction "DATA_+_3") (pintype "passive+no_connect"))
    )
    (net (code "68") (name "unconnected-(J5-DATA_--Pad2)") (class "Default")
      (node (ref "J5") (pin "2") (pinfunction "DATA_-_2") (pintype "passive+no_connect"))
    )
    (net (code "69") (name "unconnected-(J6-DATA_+-Pad3)") (class "Default")
      (node (ref "J6") (pin "3") (pinfunction "DATA_+_3") (pintype "passive+no_connect"))
    )
    (net (code "70") (name "unconnected-(J6-DATA_--Pad2)") (class "Default")
      (node (ref "J6") (pin "2") (pinfunction "DATA_-_2") (pintype "passive+no_connect"))
    )
    (net (code "71") (name "unconnected-(J7-DATA_+-Pad3)") (class "Default")
      (node (ref "J7") (pin "3") (pinfunction "DATA_+_3") (pintype "passive+no_connect"))
    )
    (net (code "72") (name "unconnected-(J7-DATA_--Pad2)") (class "Default")
      (node (ref "J7") (pin "2") (pinfunction "DATA_-_2") (pintype "passive+no_connect"))
    )
    (net (code "73") (name "unconnected-(J8-DATA_+-Pad3)") (class "Default")
      (node (ref "J8") (pin "3") (pinfunction "DATA_+_3") (pintype "passive+no_connect"))
    )
    (net (code "74") (name "unconnected-(J8-DATA_--Pad2)") (class "Default")
      (node (ref "J8") (pin "2") (pinfunction "DATA_-_2") (pintype "passive+no_connect"))
    )
    (net (code "75") (name "unconnected-(J9-DATA_+-Pad3)") (class "Default")
      (node (ref "J9") (pin "3") (pinfunction "DATA_+_3") (pintype "passive+no_connect"))
    )
    (net (code "76") (name "unconnected-(J9-DATA_--Pad2)") (class "Default")
      (node (ref "J9") (pin "2") (pinfunction "DATA_-_2") (pintype "passive+no_connect"))
    )
    (net (code "77") (name "unconnected-(J10-DATA_+-Pad3)") (class "Default")
      (node (ref "J10") (pin "3") (pinfunction "DATA_+_3") (pintype "passive+no_connect"))
    )
    (net (code "78") (name "unconnected-(J10-DATA_--Pad2)") (class "Default")
      (node (ref "J10") (pin "2") (pinfunction "DATA_-_2") (pintype "passive+no_connect"))
    )
    (net (code "79") (name "unconnected-(U11-AIN10-Pad11)") (class "Default")
      (node (ref "U11") (pin "11") (pinfunction "AIN10_11") (pintype "input+no_connect"))
    )
    (net (code "80") (name "unconnected-(U11-AIN11-Pad12)") (class "Default")
      (node (ref "U11") (pin "12") (pinfunction "AIN11_12") (pintype "input+no_connect"))
    )
    (net (code "81") (name "unconnected-(U11-AIN12-Pad13)") (class "Default")
      (node (ref "U11") (pin "13") (pinfunction "AIN12_13") (pintype "input+no_connect"))
    )
    (net (code "82") (name "unconnected-(U11-AIN13-Pad14)") (class "Default")
      (node (ref "U11") (pin "14") (pinfunction "AIN13_14") (pintype "input+no_connect"))
    )
    (net (code "83") (name "unconnected-(U11-AIN14-Pad15)") (class "Default")
      (node (ref "U11") (pin "15") (pinfunction "AIN14_15") (pintype "input+no_connect"))
    )
    (net (code "84") (name "unconnected-(U11-~{CNVST{slash}AIN15}-Pad16)") (class "Default")
      (node (ref "U11") (pin "16") (pinfunction "~{CNVST/AIN15}_16") (pintype "input+no_connect"))
    )
    (net (code "85") (name "unconnected-(U12-N.C-Pad1)") (class "Default")
      (node (ref "U12") (pin "1") (pinfunction "N.C_1") (pintype "passive+no_connect"))
    )
    (net (code "86") (name "unconnected-(U13-A0-Pad19)") (class "Default")
      (node (ref "U13") (pin "19") (pinfunction "A0_19") (pintype "input+no_connect"))
    )
    (net (code "87") (name "unconnected-(U13-A1-Pad20)") (class "Default")
      (node (ref "U13") (pin "20") (pinfunction "A1_20") (pintype "input+no_connect"))
    )
    (net (code "88") (name "unconnected-(U13-A2-Pad21)") (class "Default")
      (node (ref "U13") (pin "21") (pinfunction "A2_21") (pintype "input+no_connect"))
    )
    (net (code "89") (name "unconnected-(U13-A3-Pad22)") (class "Default")
      (node (ref "U13") (pin "22") (pinfunction "A3_22") (pintype "input+no_connect"))
    )
    (net (code "90") (name "unconnected-(U13-A4-Pad23)") (class "Default")
      (node (ref "U13") (pin "23") (pinfunction "A4_23") (pintype "input+no_connect"))
    )
    (net (code "91") (name "unconnected-(U13-A5-Pad24)") (class "Default")
      (node (ref "U13") (pin "24") (pinfunction "A5_24") (pintype "input+no_connect"))
    )
    (net (code "92") (name "unconnected-(U13-A6-Pad25)") (class "Default")
      (node (ref "U13") (pin "25") (pinfunction "A6_25") (pintype "input+no_connect"))
    )
    (net (code "93") (name "unconnected-(U13-A7-Pad26)") (class "Default")
      (node (ref "U13") (pin "26") (pinfunction "A7_26") (pintype "input+no_connect"))
    )
    (net (code "94") (name "unconnected-(U13-D0{slash}RX-Pad2)") (class "Default")
      (node (ref "U13") (pin "2") (pinfunction "D0/RX_2") (pintype "bidirectional+no_connect"))
    )
    (net (code "95") (name "unconnected-(U13-D1{slash}TX-Pad1)") (class "Default")
      (node (ref "U13") (pin "1") (pinfunction "D1/TX_1") (pintype "bidirectional+no_connect"))
    )
    (net (code "96") (name "unconnected-(U13-D3-Pad6)") (class "Default")
      (node (ref "U13") (pin "6") (pinfunction "D3_6") (pintype "bidirectional+no_connect"))
    )
    (net (code "97") (name "unconnected-(U13-D4-Pad7)") (class "Default")
      (node (ref "U13") (pin "7") (pinfunction "D4_7") (pintype "bidirectional+no_connect"))
    )
    (net (code "98") (name "unconnected-(U13-RESET-Pad3)") (class "Default")
      (node (ref "U13") (pin "3") (pinfunction "RESET_3") (pintype "input+no_connect"))
    )
    (net (code "99") (name "unconnected-(U13-RESET-Pad28)") (class "Default")
      (node (ref "U13") (pin "28") (pinfunction "RESET_28") (pintype "input+no_connect"))
    )
    (net (code "100") (name "unconnected-(U13-VIN-Pad30)") (class "Default")
      (node (ref "U13") (pin "30") (pinfunction "VIN_30") (pintype "input+no_connect"))
    )
  )
)
